# IR_Remote_Keypad.net
KiCad netlist of a schematic drawn in Altium Designer
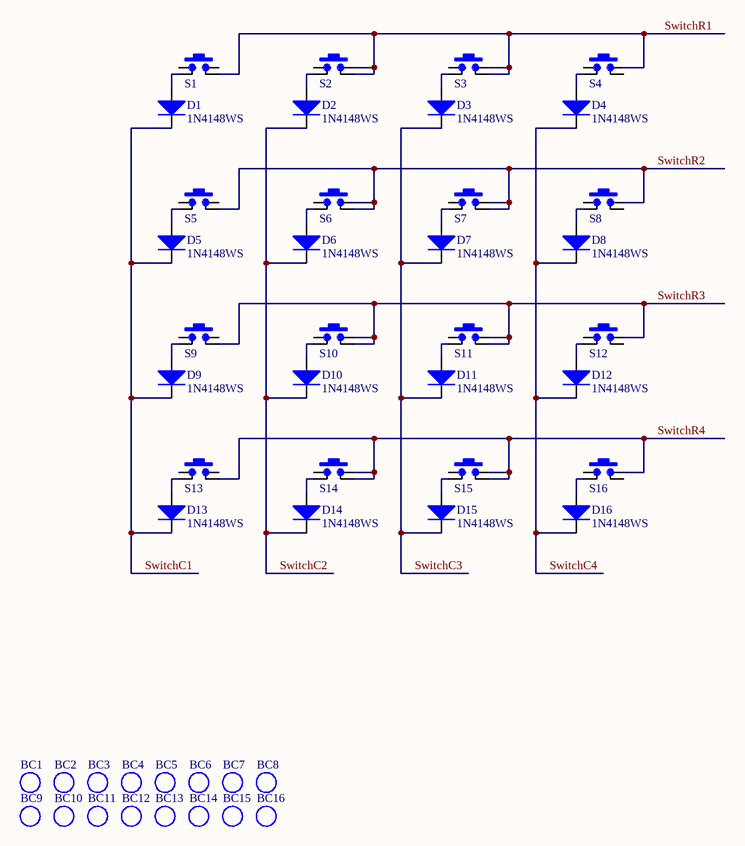
[diagram p0: IR_Remote_Keypad.SchDoc]

(export (version "E")
  (design (tool "Eeschema 10.0.6"))
  (components
    (comp (ref "BC1")
      (value "Button cap")
      (footprint "Button-cap-with-skirt")
      (description "6.2mm x 6mm (WxH) button cap")
      (libsource (lib "MyLibrary") (part "Small Button Cap"))
    )
    (comp (ref "BC2")
      (value "Button cap")
      (footprint "Button-cap-with-skirt")
      (description "6.2mm x 6mm (WxH) button cap")
      (libsource (lib "MyLibrary") (part "Small Button Cap"))
    )
    (comp (ref "BC3")
      (value "Button cap")
      (footprint "Button-cap-with-skirt")
      (description "6.2mm x 6mm (WxH) button cap")
      (libsource (lib "MyLibrary") (part "Small Button Cap"))
    )
    (comp (ref "BC4")
      (value "Button cap")
      (footprint "Button-cap-with-skirt")
      (description "6.2mm x 6mm (WxH) button cap")
      (libsource (lib "MyLibrary") (part "Small Button Cap"))
    )
    (comp (ref "BC5")
      (value "Button cap")
      (footprint "Button-cap-with-skirt")
      (description "6.2mm x 6mm (WxH) button cap")
      (libsource (lib "MyLibrary") (part "Small Button Cap"))
    )
    (comp (ref "BC6")
      (value "Button cap")
      (footprint "Button-cap-with-skirt")
      (description "6.2mm x 6mm (WxH) button cap")
      (libsource (lib "MyLibrary") (part "Small Button Cap"))
    )
    (comp (ref "BC7")
      (value "Button cap")
      (footprint "Button-cap-with-skirt")
      (description "6.2mm x 6mm (WxH) button cap")
      (libsource (lib "MyLibrary") (part "Small Button Cap"))
    )
    (comp (ref "BC8")
      (value "Button cap")
      (footprint "Button-cap-with-skirt")
      (description "6.2mm x 6mm (WxH) button cap")
      (libsource (lib "MyLibrary") (part "Small Button Cap"))
    )
    (comp (ref "BC9")
      (value "Button cap")
      (footprint "Button-cap-with-skirt")
      (description "6.2mm x 6mm (WxH) button cap")
      (libsource (lib "MyLibrary") (part "Small Button Cap"))
    )
    (comp (ref "BC10")
      (value "Button cap")
      (footprint "Button-cap-with-skirt")
      (description "6.2mm x 6mm (WxH) button cap")
      (libsource (lib "MyLibrary") (part "Small Button Cap"))
    )
    (comp (ref "BC11")
      (value "Button cap")
      (footprint "Button-cap-with-skirt")
      (description "6.2mm x 6mm (WxH) button cap")
      (libsource (lib "MyLibrary") (part "Small Button Cap"))
    )
    (comp (ref "BC12")
      (value "Button cap")
      (footprint "Button-cap-with-skirt")
      (description "6.2mm x 6mm (WxH) button cap")
      (libsource (lib "MyLibrary") (part "Small Button Cap"))
    )
    (comp (ref "BC13")
      (value "Button cap")
      (footprint "Button-cap-with-skirt")
      (description "6.2mm x 6mm (WxH) button cap")
      (libsource (lib "MyLibrary") (part "Small Button Cap"))
    )
    (comp (ref "BC14")
      (value "Button cap")
      (footprint "Button-cap-with-skirt")
      (description "6.2mm x 6mm (WxH) button cap")
      (libsource (lib "MyLibrary") (part "Small Button Cap"))
    )
    (comp (ref "BC15")
      (value "Button cap")
      (footprint "Button-cap-with-skirt")
      (description "6.2mm x 6mm (WxH) button cap")
      (libsource (lib "MyLibrary") (part "Small Button Cap"))
    )
    (comp (ref "BC16")
      (value "Button cap")
      (footprint "Button-cap-with-skirt")
      (description "6.2mm x 6mm (WxH) button cap")
      (libsource (lib "MyLibrary") (part "Small Button Cap"))
    )
    (comp (ref "D1")
      (value "1N4148WS")
      (footprint "SOD-323")
      (description "Diode - Switching 100V 150mA 1.25V@150mA 4ns SOD-323")
      (libsource (lib "MyLibrary") (part "1N4148WS"))
    )
    (comp (ref "D2")
      (value "1N4148WS")
      (footprint "SOD-323")
      (description "Diode - Switching 100V 150mA 1.25V@150mA 4ns SOD-323")
      (libsource (lib "MyLibrary") (part "1N4148WS"))
    )
    (comp (ref "D3")
      (value "1N4148WS")
      (footprint "SOD-323")
      (description "Diode - Switching 100V 150mA 1.25V@150mA 4ns SOD-323")
      (libsource (lib "MyLibrary") (part "1N4148WS"))
    )
    (comp (ref "D4")
      (value "1N4148WS")
      (footprint "SOD-323")
      (description "Diode - Switching 100V 150mA 1.25V@150mA 4ns SOD-323")
      (libsource (lib "MyLibrary") (part "1N4148WS"))
    )
    (comp (ref "D5")
      (value "1N4148WS")
      (footprint "SOD-323")
      (description "Diode - Switching 100V 150mA 1.25V@150mA 4ns SOD-323")
      (libsource (lib "MyLibrary") (part "1N4148WS"))
    )
    (comp (ref "D6")
      (value "1N4148WS")
      (footprint "SOD-323")
      (description "Diode - Switching 100V 150mA 1.25V@150mA 4ns SOD-323")
      (libsource (lib "MyLibrary") (part "1N4148WS"))
    )
    (comp (ref "D7")
      (value "1N4148WS")
      (footprint "SOD-323")
      (description "Diode - Switching 100V 150mA 1.25V@150mA 4ns SOD-323")
      (libsource (lib "MyLibrary") (part "1N4148WS"))
    )
    (comp (ref "D8")
      (value "1N4148WS")
      (footprint "SOD-323")
      (description "Diode - Switching 100V 150mA 1.25V@150mA 4ns SOD-323")
      (libsource (lib "MyLibrary") (part "1N4148WS"))
    )
    (comp (ref "D9")
      (value "1N4148WS")
      (footprint "SOD-323")
      (description "Diode - Switching 100V 150mA 1.25V@150mA 4ns SOD-323")
      (libsource (lib "MyLibrary") (part "1N4148WS"))
    )
    (comp (ref "D10")
      (value "1N4148WS")
      (footprint "SOD-323")
      (description "Diode - Switching 100V 150mA 1.25V@150mA 4ns SOD-323")
      (libsource (lib "MyLibrary") (part "1N4148WS"))
    )
    (comp (ref "D11")
      (value "1N4148WS")
      (footprint "SOD-323")
      (description "Diode - Switching 100V 150mA 1.25V@150mA 4ns SOD-323")
      (libsource (lib "MyLibrary") (part "1N4148WS"))
    )
    (comp (ref "D12")
      (value "1N4148WS")
      (footprint "SOD-323")
      (description "Diode - Switching 100V 150mA 1.25V@150mA 4ns SOD-323")
      (libsource (lib "MyLibrary") (part "1N4148WS"))
    )
    (comp (ref "D13")
      (value "1N4148WS")
      (footprint "SOD-323")
      (description "Diode - Switching 100V 150mA 1.25V@150mA 4ns SOD-323")
      (libsource (lib "MyLibrary") (part "1N4148WS"))
    )
    (comp (ref "D14")
      (value "1N4148WS")
      (footprint "SOD-323")
      (description "Diode - Switching 100V 150mA 1.25V@150mA 4ns SOD-323")
      (libsource (lib "MyLibrary") (part "1N4148WS"))
    )
    (comp (ref "D15")
      (value "1N4148WS")
      (footprint "SOD-323")
      (description "Diode - Switching 100V 150mA 1.25V@150mA 4ns SOD-323")
      (libsource (lib "MyLibrary") (part "1N4148WS"))
    )
    (comp (ref "D16")
      (value "1N4148WS")
      (footprint "SOD-323")
      (description "Diode - Switching 100V 150mA 1.25V@150mA 4ns SOD-323")
      (libsource (lib "MyLibrary") (part "1N4148WS"))
    )
    (comp (ref "S1")
      (value "SW_SMT_14mm")
      (footprint "SW_SMT_14mm")
      (description "SMT Switch gull-wing leads common")
      (libsource (lib "MySchLib") (part "SW_PB_SMT"))
    )
    (comp (ref "S2")
      (value "SW_SMT_14mm")
      (footprint "SW_SMT_14mm")
      (description "SMT Switch gull-wing leads common")
      (libsource (lib "MySchLib") (part "SW_PB_SMT"))
    )
    (comp (ref "S3")
      (value "SW_SMT_14mm")
      (footprint "SW_SMT_14mm")
      (description "SMT Switch gull-wing leads common")
      (libsource (lib "MySchLib") (part "SW_PB_SMT"))
    )
    (comp (ref "S4")
      (value "SW_SMT_14mm")
      (footprint "SW_SMT_14mm")
      (description "SMT Switch gull-wing leads common")
      (libsource (lib "MySchLib") (part "SW_PB_SMT"))
    )
    (comp (ref "S5")
      (value "SW_SMT_14mm")
      (footprint "SW_SMT_14mm")
      (description "SMT Switch gull-wing leads common")
      (libsource (lib "MySchLib") (part "SW_PB_SMT"))
    )
    (comp (ref "S6")
      (value "SW_SMT_14mm")
      (footprint "SW_SMT_14mm")
      (description "SMT Switch gull-wing leads common")
      (libsource (lib "MySchLib") (part "SW_PB_SMT"))
    )
    (comp (ref "S7")
      (value "SW_SMT_14mm")
      (footprint "SW_SMT_14mm")
      (description "SMT Switch gull-wing leads common")
      (libsource (lib "MySchLib") (part "SW_PB_SMT"))
    )
    (comp (ref "S8")
      (value "SW_SMT_14mm")
      (footprint "SW_SMT_14mm")
      (description "SMT Switch gull-wing leads common")
      (libsource (lib "MySchLib") (part "SW_PB_SMT"))
    )
    (comp (ref "S9")
      (value "SW_SMT_14mm")
      (footprint "SW_SMT_14mm")
      (description "SMT Switch gull-wing leads common")
      (libsource (lib "MySchLib") (part "SW_PB_SMT"))
    )
    (comp (ref "S10")
      (value "SW_SMT_14mm")
      (footprint "SW_SMT_14mm")
      (description "SMT Switch gull-wing leads common")
      (libsource (lib "MySchLib") (part "SW_PB_SMT"))
    )
    (comp (ref "S11")
      (value "SW_SMT_14mm")
      (footprint "SW_SMT_14mm")
      (description "SMT Switch gull-wing leads common")
      (libsource (lib "MySchLib") (part "SW_PB_SMT"))
    )
    (comp (ref "S12")
      (value "SW_SMT_14mm")
      (footprint "SW_SMT_14mm")
      (description "SMT Switch gull-wing leads common")
      (libsource (lib "MySchLib") (part "SW_PB_SMT"))
    )
    (comp (ref "S13")
      (value "SW_SMT_14mm")
      (footprint "SW_SMT_14mm")
      (description "SMT Switch gull-wing leads common")
      (libsource (lib "MySchLib") (part "SW_PB_SMT"))
    )
    (comp (ref "S14")
      (value "SW_SMT_14mm")
      (footprint "SW_SMT_14mm")
      (description "SMT Switch gull-wing leads common")
      (libsource (lib "MySchLib") (part "SW_PB_SMT"))
    )
    (comp (ref "S15")
      (value "SW_SMT_14mm")
      (footprint "SW_SMT_14mm")
      (description "SMT Switch gull-wing leads common")
      (libsource (lib "MySchLib") (part "SW_PB_SMT"))
    )
    (comp (ref "S16")
      (value "SW_SMT_14mm")
      (footprint "SW_SMT_14mm")
      (description "SMT Switch gull-wing leads common")
      (libsource (lib "MySchLib") (part "SW_PB_SMT"))
    )
  )
  (nets
    (net (code "1") (name "/SwitchC1") (class "Default")
      (node (ref "D1") (pin "K") (pinfunction "K_K") (pintype "passive"))
      (node (ref "D13") (pin "K") (pinfunction "K_K") (pintype "passive"))
      (node (ref "D5") (pin "K") (pinfunction "K_K") (pintype "passive"))
      (node (ref "D9") (pin "K") (pinfunction "K_K") (pintype "passive"))
    )
    (net (code "2") (name "/SwitchC2") (class "Default")
      (node (ref "D10") (pin "K") (pinfunction "K_K") (pintype "passive"))
      (node (ref "D14") (pin "K") (pinfunction "K_K") (pintype "passive"))
      (node (ref "D2") (pin "K") (pinfunction "K_K") (pintype "passive"))
      (node (ref "D6") (pin "K") (pinfunction "K_K") (pintype "passive"))
    )
    (net (code "3") (name "/SwitchC3") (class "Default")
      (node (ref "D11") (pin "K") (pinfunction "K_K") (pintype "passive"))
      (node (ref "D15") (pin "K") (pinfunction "K_K") (pintype "passive"))
      (node (ref "D3") (pin "K") (pinfunction "K_K") (pintype "passive"))
      (node (ref "D7") (pin "K") (pinfunction "K_K") (pintype "passive"))
    )
    (net (code "4") (name "/SwitchC4") (class "Default")
      (node (ref "D12") (pin "K") (pinfunction "K_K") (pintype "passive"))
      (node (ref "D16") (pin "K") (pinfunction "K_K") (pintype "passive"))
      (node (ref "D4") (pin "K") (pinfunction "K_K") (pintype "passive"))
      (node (ref "D8") (pin "K") (pinfunction "K_K") (pintype "passive"))
    )
    (net (code "5") (name "/SwitchR1") (class "Default")
      (node (ref "S1") (pin "2") (pinfunction "2_2") (pintype "passive"))
      (node (ref "S2") (pin "2") (pinfunction "2_2") (pintype "passive"))
      (node (ref "S2") (pin "2b") (pinfunction "2b_2b") (pintype "passive"))
      (node (ref "S3") (pin "2") (pinfunction "2_2") (pintype "passive"))
      (node (ref "S3") (pin "2b") (pinfunction "2b_2b") (pintype "passive"))
      (node (ref "S4") (pin "2b") (pinfunction "2b_2b") (pintype "passive"))
    )
    (net (code "6") (name "/SwitchR2") (class "Default")
      (node (ref "S5") (pin "1") (pinfunction "1_1") (pintype "passive"))
      (node (ref "S6") (pin "1") (pinfunction "1_1") (pintype "passive"))
      (node (ref "S6") (pin "1b") (pinfunction "1b_1b") (pintype "passive"))
      (node (ref "S7") (pin "1") (pinfunction "1_1") (pintype "passive"))
      (node (ref "S7") (pin "1b") (pinfunction "1b_1b") (pintype "passive"))
      (node (ref "S8") (pin "1b") (pinfunction "1b_1b") (pintype "passive"))
    )
    (net (code "7") (name "/SwitchR3") (class "Default")
      (node (ref "S10") (pin "1") (pinfunction "1_1") (pintype "passive"))
      (node (ref "S10") (pin "1b") (pinfunction "1b_1b") (pintype "passive"))
      (node (ref "S11") (pin "1") (pinfunction "1_1") (pintype "passive"))
      (node (ref "S11") (pin "1b") (pinfunction "1b_1b") (pintype "passive"))
      (node (ref "S12") (pin "1b") (pinfunction "1b_1b") (pintype "passive"))
      (node (ref "S9") (pin "1") (pinfunction "1_1") (pintype "passive"))
    )
    (net (code "8") (name "/SwitchR4") (class "Default")
      (node (ref "S13") (pin "1") (pinfunction "1_1") (pintype "passive"))
      (node (ref "S14") (pin "1") (pinfunction "1_1") (pintype "passive"))
      (node (ref "S14") (pin "1b") (pinfunction "1b_1b") (pintype "passive"))
      (node (ref "S15") (pin "1") (pinfunction "1_1") (pintype "passive"))
      (node (ref "S15") (pin "1b") (pinfunction "1b_1b") (pintype "passive"))
      (node (ref "S16") (pin "1b") (pinfunction "1b_1b") (pintype "passive"))
    )
    (net (code "9") (name "Net-(D1-PadA)") (class "Default")
      (node (ref "D1") (pin "A") (pinfunction "A_A") (pintype "passive"))
      (node (ref "S1") (pin "1") (pinfunction "1_1") (pintype "passive"))
    )
    (net (code "10") (name "Net-(D2-PadA)") (class "Default")
      (node (ref "D2") (pin "A") (pinfunction "A_A") (pintype "passive"))
      (node (ref "S2") (pin "1") (pinfunction "1_1") (pintype "passive"))
    )
    (net (code "11") (name "Net-(D3-PadA)") (class "Default")
      (node (ref "D3") (pin "A") (pinfunction "A_A") (pintype "passive"))
      (node (ref "S3") (pin "1") (pinfunction "1_1") (pintype "passive"))
    )
    (net (code "12") (name "Net-(D4-PadA)") (class "Default")
      (node (ref "D4") (pin "A") (pinfunction "A_A") (pintype "passive"))
      (node (ref "S4") (pin "1") (pinfunction "1_1") (pintype "passive"))
    )
    (net (code "13") (name "Net-(D5-PadA)") (class "Default")
      (node (ref "D5") (pin "A") (pinfunction "A_A") (pintype "passive"))
      (node (ref "S5") (pin "2") (pinfunction "2_2") (pintype "passive"))
    )
    (net (code "14") (name "Net-(D6-PadA)") (class "Default")
      (node (ref "D6") (pin "A") (pinfunction "A_A") (pintype "passive"))
      (node (ref "S6") (pin "2") (pinfunction "2_2") (pintype "passive"))
    )
    (net (code "15") (name "Net-(D7-PadA)") (class "Default")
      (node (ref "D7") (pin "A") (pinfunction "A_A") (pintype "passive"))
      (node (ref "S7") (pin "2") (pinfunction "2_2") (pintype "passive"))
    )
    (net (code "16") (name "Net-(D8-PadA)") (class "Default")
      (node (ref "D8") (pin "A") (pinfunction "A_A") (pintype "passive"))
      (node (ref "S8") (pin "2") (pinfunction "2_2") (pintype "passive"))
    )
    (net (code "17") (name "Net-(D9-PadA)") (class "Default")
      (node (ref "D9") (pin "A") (pinfunction "A_A") (pintype "passive"))
      (node (ref "S9") (pin "2") (pinfunction "2_2") (pintype "passive"))
    )
    (net (code "18") (name "Net-(D10-PadA)") (class "Default")
      (node (ref "D10") (pin "A") (pinfunction "A_A") (pintype "passive"))
      (node (ref "S10") (pin "2") (pinfunction "2_2") (pintype "passive"))
    )
    (net (code "19") (name "Net-(D11-PadA)") (class "Default")
      (node (ref "D11") (pin "A") (pinfunction "A_A") (pintype "passive"))
      (node (ref "S11") (pin "2") (pinfunction "2_2") (pintype "passive"))
    )
    (net (code "20") (name "Net-(D12-PadA)") (class "Default")
      (node (ref "D12") (pin "A") (pinfunction "A_A") (pintype "passive"))
      (node (ref "S12") (pin "2") (pinfunction "2_2") (pintype "passive"))
    )
    (net (code "21") (name "Net-(D13-PadA)") (class "Default")
      (node (ref "D13") (pin "A") (pinfunction "A_A") (pintype "passive"))
      (node (ref "S13") (pin "2") (pinfunction "2_2") (pintype "passive"))
    )
    (net (code "22") (name "Net-(D14-PadA)") (class "Default")
      (node (ref "D14") (pin "A") (pinfunction "A_A") (pintype "passive"))
      (node (ref "S14") (pin "2") (pinfunction "2_2") (pintype "passive"))
    )
    (net (code "23") (name "Net-(D15-PadA)") (class "Default")
      (node (ref "D15") (pin "A") (pinfunction "A_A") (pintype "passive"))
      (node (ref "S15") (pin "2") (pinfunction "2_2") (pintype "passive"))
    )
    (net (code "24") (name "Net-(D16-PadA)") (class "Default")
      (node (ref "D16") (pin "A") (pinfunction "A_A") (pintype "passive"))
      (node (ref "S16") (pin "2") (pinfunction "2_2") (pintype "passive"))
    )
    (net (code "25") (name "unconnected-(S1-Pad1b)") (class "Default")
      (node (ref "S1") (pin "1b") (pinfunction "1b_1b") (pintype "passive"))
    )
    (net (code "26") (name "unconnected-(S1-Pad2b)") (class "Default")
      (node (ref "S1") (pin "2b") (pinfunction "2b_2b") (pintype "passive"))
    )
    (net (code "27") (name "unconnected-(S2-Pad1b)") (class "Default")
      (node (ref "S2") (pin "1b") (pinfunction "1b_1b") (pintype "passive"))
    )
    (net (code "28") (name "unconnected-(S3-Pad1b)") (class "Default")
      (node (ref "S3") (pin "1b") (pinfunction "1b_1b") (pintype "passive"))
    )
    (net (code "29") (name "unconnected-(S4-Pad1b)") (class "Default")
      (node (ref "S4") (pin "1b") (pinfunction "1b_1b") (pintype "passive"))
    )
    (net (code "30") (name "unconnected-(S4-Pad2)") (class "Default")
      (node (ref "S4") (pin "2") (pinfunction "2_2") (pintype "passive"))
    )
    (net (code "31") (name "unconnected-(S5-Pad1b)") (class "Default")
      (node (ref "S5") (pin "1b") (pinfunction "1b_1b") (pintype "passive"))
    )
    (net (code "32") (name "unconnected-(S5-Pad2b)") (class "Default")
      (node (ref "S5") (pin "2b") (pinfunction "2b_2b") (pintype "passive"))
    )
    (net (code "33") (name "unconnected-(S6-Pad2b)") (class "Default")
      (node (ref "S6") (pin "2b") (pinfunction "2b_2b") (pintype "passive"))
    )
    (net (code "34") (name "unconnected-(S7-Pad2b)") (class "Default")
      (node (ref "S7") (pin "2b") (pinfunction "2b_2b") (pintype "passive"))
    )
    (net (code "35") (name "unconnected-(S8-Pad1)") (class "Default")
      (node (ref "S8") (pin "1") (pinfunction "1_1") (pintype "passive"))
    )
    (net (code "36") (name "unconnected-(S8-Pad2b)") (class "Default")
      (node (ref "S8") (pin "2b") (pinfunction "2b_2b") (pintype "passive"))
    )
    (net (code "37") (name "unconnected-(S9-Pad1b)") (class "Default")
      (node (ref "S9") (pin "1b") (pinfunction "1b_1b") (pintype "passive"))
    )
    (net (code "38") (name "unconnected-(S9-Pad2b)") (class "Default")
      (node (ref "S9") (pin "2b") (pinfunction "2b_2b") (pintype "passive"))
    )
    (net (code "39") (name "unconnected-(S10-Pad2b)") (class "Default")
      (node (ref "S10") (pin "2b") (pinfunction "2b_2b") (pintype "passive"))
    )
    (net (code "40") (name "unconnected-(S11-Pad2b)") (class "Default")
      (node (ref "S11") (pin "2b") (pinfunction "2b_2b") (pintype "passive"))
    )
    (net (code "41") (name "unconnected-(S12-Pad1)") (class "Default")
      (node (ref "S12") (pin "1") (pinfunction "1_1") (pintype "passive"))
    )
    (net (code "42") (name "unconnected-(S12-Pad2b)") (class "Default")
      (node (ref "S12") (pin "2b") (pinfunction "2b_2b") (pintype "passive"))
    )
    (net (code "43") (name "unconnected-(S13-Pad1b)") (class "Default")
      (node (ref "S13") (pin "1b") (pinfunction "1b_1b") (pintype "passive"))
    )
    (net (code "44") (name "unconnected-(S13-Pad2b)") (class "Default")
      (node (ref "S13") (pin "2b") (pinfunction "2b_2b") (pintype "passive"))
    )
    (net (code "45") (name "unconnected-(S14-Pad2b)") (class "Default")
      (node (ref "S14") (pin "2b") (pinfunction "2b_2b") (pintype "passive"))
    )
    (net (code "46") (name "unconnected-(S15-Pad2b)") (class "Default")
      (node (ref "S15") (pin "2b") (pinfunction "2b_2b") (pintype "passive"))
    )
    (net (code "47") (name "unconnected-(S16-Pad1)") (class "Default")
      (node (ref "S16") (pin "1") (pinfunction "1_1") (pintype "passive"))
    )
    (net (code "48") (name "unconnected-(S16-Pad2b)") (class "Default")
      (node (ref "S16") (pin "2b") (pinfunction "2b_2b") (pintype "passive"))
    )
  )
)
